# LM317_Voltage_supply_2020-10-09_18-57-09.net
KiCad netlist of a schematic drawn in EasyEDA
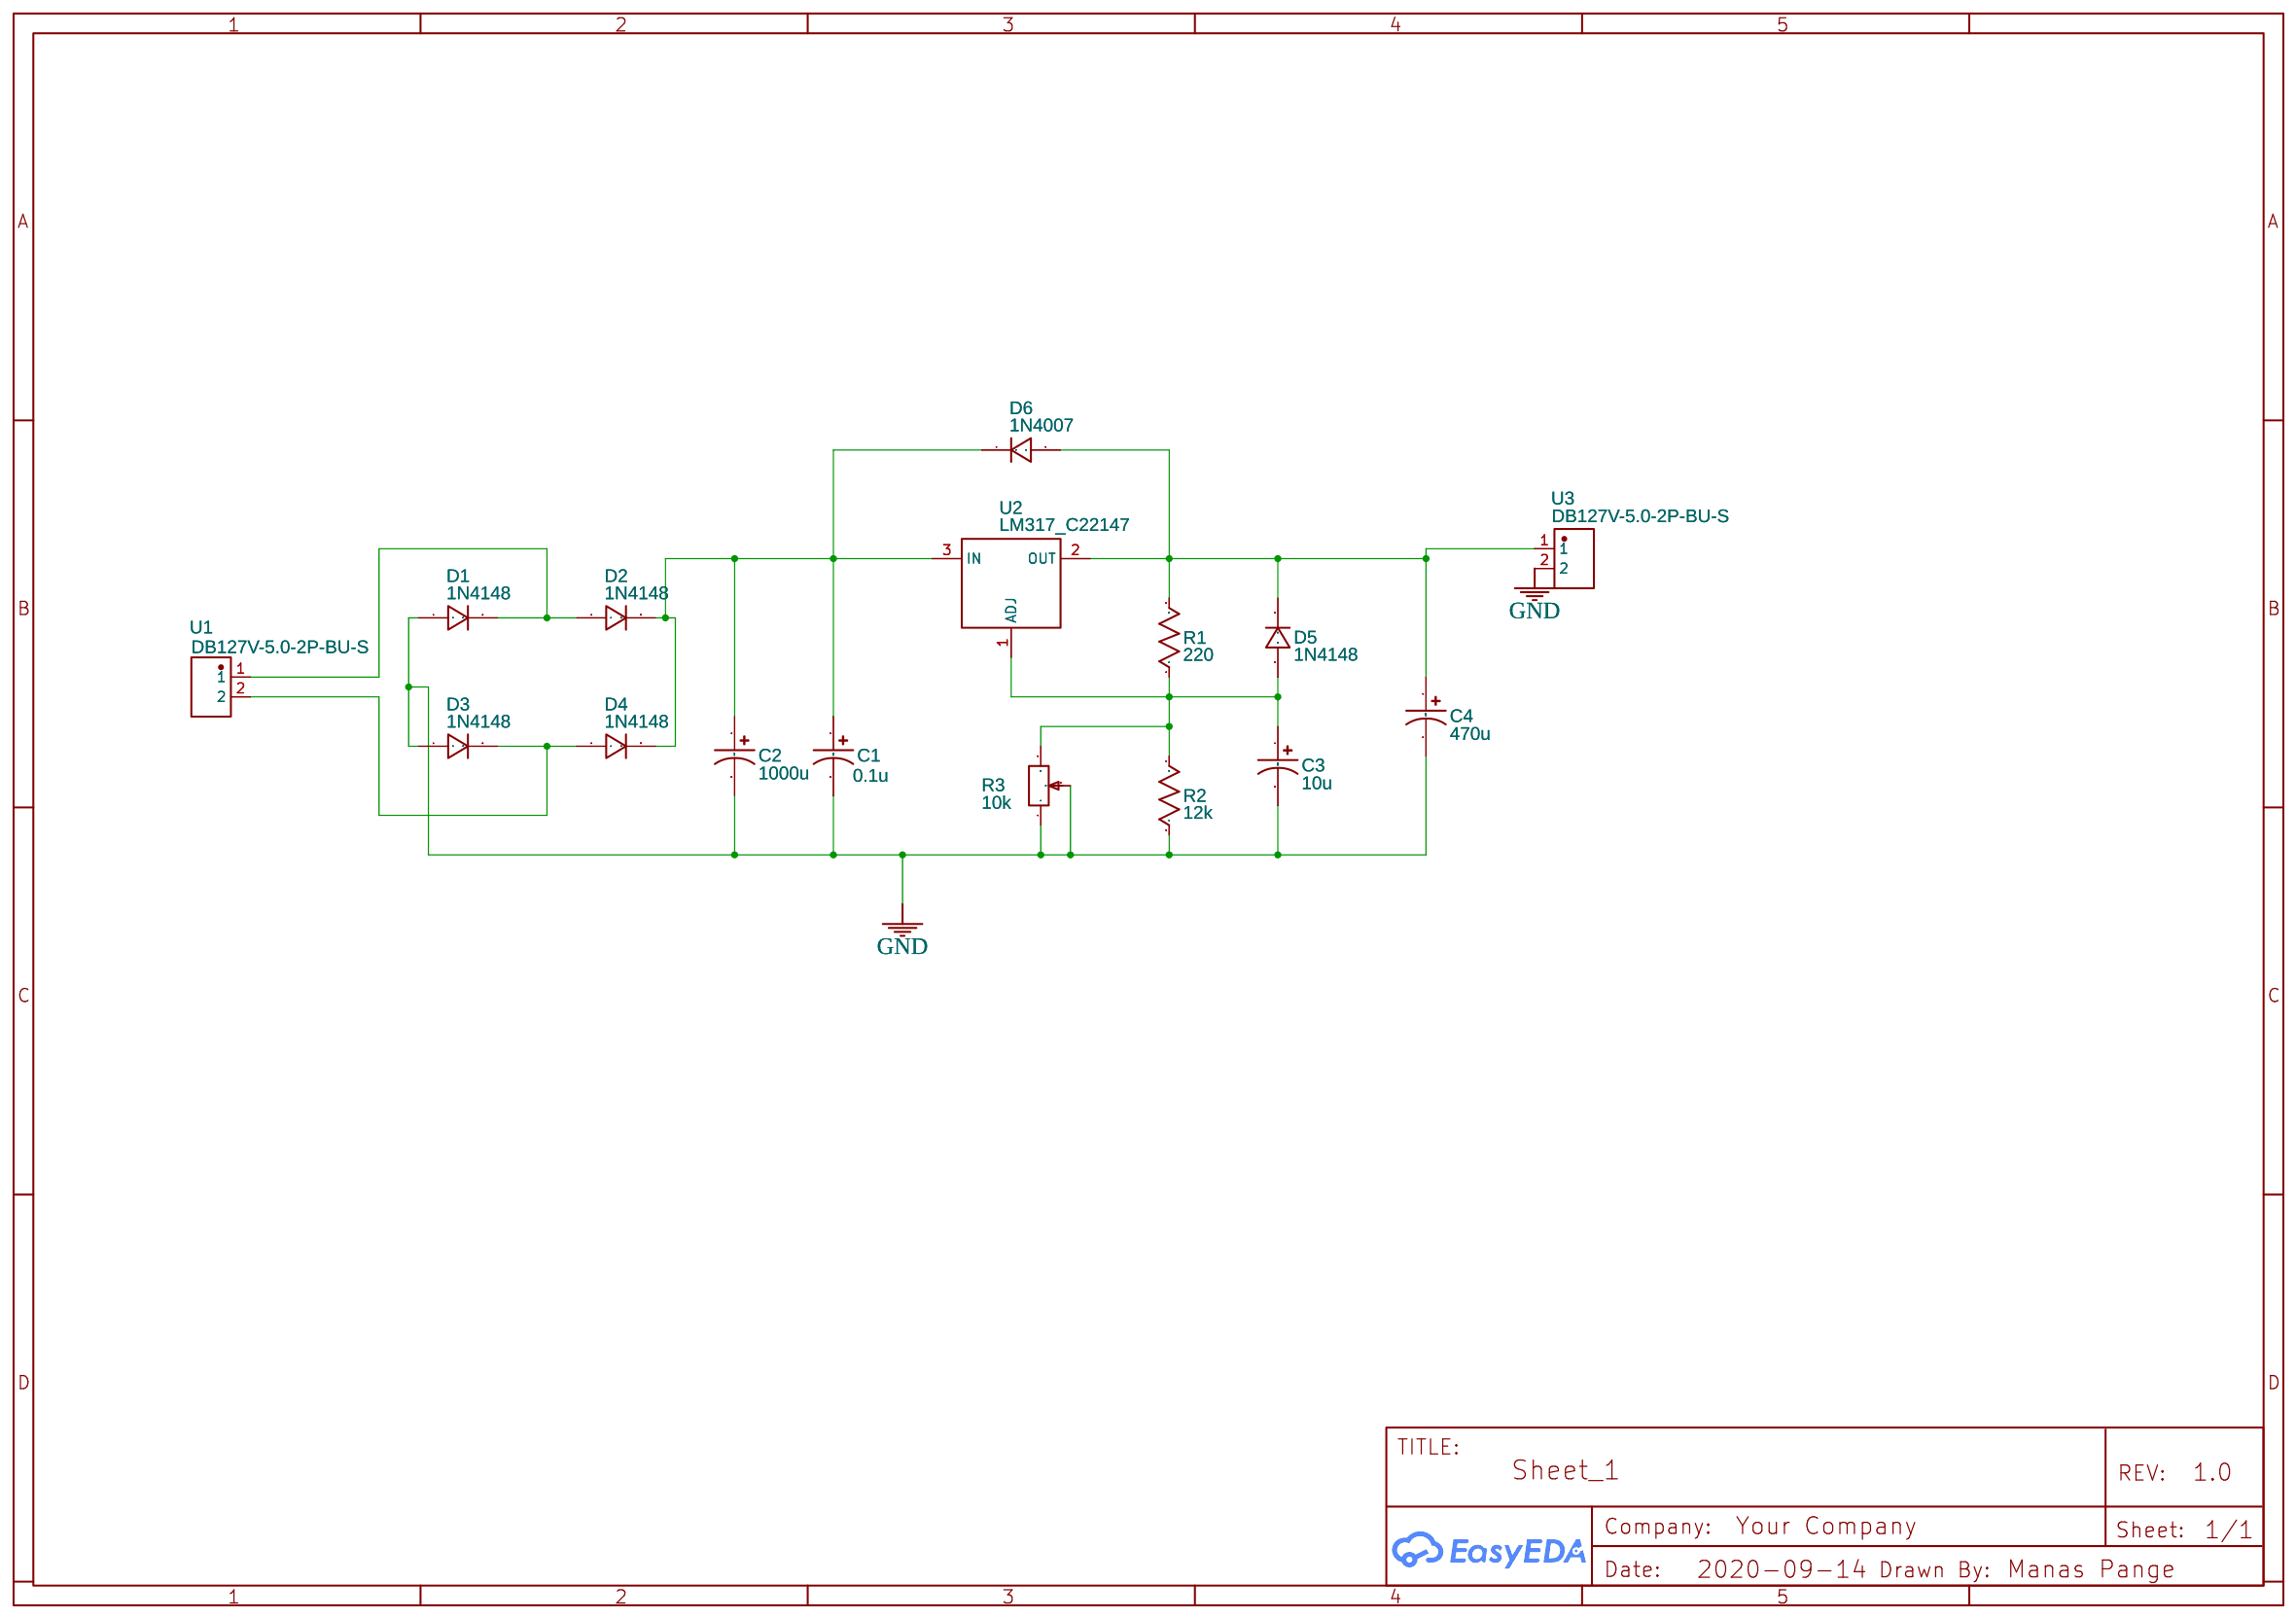
[diagram p0: schematic sheet]

(export (version "E")
  (design (tool "Eeschema 10.0.6"))
  (components
    (comp (ref "C1") (value "0.1u") (libsource (lib "") (part "CE_TH_D6.3×F2.5_US")))
    (comp (ref "C2") (value "1000u") (libsource (lib "") (part "CE_TH_D6.3×F2.5_US")))
    (comp (ref "C3") (value "10u") (libsource (lib "") (part "CE_TH_D6.3×F2.5_US")))
    (comp (ref "C4") (value "470u") (libsource (lib "") (part "CE_TH_D6.3×F2.5_US")))
    (comp (ref "D1")
      (value "1N4148")
      (fields (field (name "BOM_Supplier Part") "C14516"))
      (libsource (lib "") (part "1N4148"))
    )
    (comp (ref "D2")
      (value "1N4148")
      (fields (field (name "BOM_Supplier Part") "C14516"))
      (libsource (lib "") (part "1N4148"))
    )
    (comp (ref "D3")
      (value "1N4148")
      (fields (field (name "BOM_Supplier Part") "C14516"))
      (libsource (lib "") (part "1N4148"))
    )
    (comp (ref "D4")
      (value "1N4148")
      (fields (field (name "BOM_Supplier Part") "C14516"))
      (libsource (lib "") (part "1N4148"))
    )
    (comp (ref "D5")
      (value "1N4148")
      (fields (field (name "BOM_Supplier Part") "C14516"))
      (libsource (lib "") (part "1N4148_1"))
    )
    (comp (ref "D6")
      (value "1N4007")
      (fields (field (name "BOM_Supplier Part") "C106903"))
      (libsource (lib "") (part "1N4007"))
    )
    (comp (ref "R1") (value "220") (libsource (lib "") (part "R_AXIAL-0.3_US")))
    (comp (ref "R2") (value "12k") (libsource (lib "") (part "R_AXIAL-0.3_US")))
    (comp (ref "R3")
      (value "10k")
      (fields
        (field (name "BOM_Manufacturer Part") "RK1631110TT3")
        (field (name "BOM_Supplier Part") "C370977")
      )
      (libsource (lib "") (part "RK1631110TT3"))
    )
    (comp (ref "U1")
      (value "DB127V-5.0-2P-BU-S")
      (fields (field (name "BOM_Supplier Part") "C500019"))
      (libsource (lib "") (part "DB127V-5.0-2P-BU-S_1"))
    )
    (comp (ref "U2")
      (value "LM317_C22147")
      (fields (field (name "BOM_Manufacturer Part") "LM317") (field (name "BOM_Supplier Part") "C22147"))
      (libsource (lib "") (part "LM317_C22147"))
    )
    (comp (ref "U3")
      (value "DB127V-5.0-2P-BU-S")
      (fields (field (name "BOM_Supplier Part") "C500019"))
      (libsource (lib "") (part "DB127V-5.0-2P-BU-S"))
    )
  )
  (nets
    (net (code "1") (name "GND") (class "Default")
      (node (ref "C1") (pin "2") (pinfunction "2_2") (pintype "unspecified"))
      (node (ref "C2") (pin "2") (pinfunction "2_2") (pintype "unspecified"))
      (node (ref "C3") (pin "2") (pinfunction "2_2") (pintype "unspecified"))
      (node (ref "C4") (pin "2") (pinfunction "2_2") (pintype "unspecified"))
      (node (ref "D1") (pin "1") (pinfunction "1_1") (pintype "unspecified"))
      (node (ref "D3") (pin "1") (pinfunction "1_1") (pintype "unspecified"))
      (node (ref "R2") (pin "1") (pinfunction "1_1") (pintype "unspecified"))
      (node (ref "R3") (pin "1") (pinfunction "1_1") (pintype "input"))
      (node (ref "R3") (pin "2") (pinfunction "2_2") (pintype "input"))
      (node (ref "U3") (pin "2") (pinfunction "2_2") (pintype "unspecified"))
    )
    (net (code "2") (name "Net-(D1-Pad2)") (class "Default")
      (node (ref "D1") (pin "2") (pinfunction "2_2") (pintype "unspecified"))
      (node (ref "D2") (pin "1") (pinfunction "1_1") (pintype "unspecified"))
      (node (ref "U1") (pin "1") (pinfunction "1_1") (pintype "unspecified"))
    )
    (net (code "3") (name "Net-(D3-Pad2)") (class "Default")
      (node (ref "D3") (pin "2") (pinfunction "2_2") (pintype "unspecified"))
      (node (ref "D4") (pin "1") (pinfunction "1_1") (pintype "unspecified"))
      (node (ref "U1") (pin "2") (pinfunction "2_2") (pintype "unspecified"))
    )
    (net (code "4") (name "Net-(U2-ADJ)") (class "Default")
      (node (ref "C3") (pin "1") (pinfunction "1_1") (pintype "unspecified"))
      (node (ref "D5") (pin "1") (pinfunction "1_1") (pintype "unspecified"))
      (node (ref "R1") (pin "1") (pinfunction "1_1") (pintype "unspecified"))
      (node (ref "R2") (pin "2") (pinfunction "2_2") (pintype "unspecified"))
      (node (ref "R3") (pin "3") (pinfunction "3_3") (pintype "input"))
      (node (ref "U2") (pin "1") (pinfunction "ADJ_1") (pintype "input"))
    )
    (net (code "5") (name "Net-(U2-IN)") (class "Default")
      (node (ref "C1") (pin "1") (pinfunction "1_1") (pintype "unspecified"))
      (node (ref "C2") (pin "1") (pinfunction "1_1") (pintype "unspecified"))
      (node (ref "D2") (pin "2") (pinfunction "2_2") (pintype "unspecified"))
      (node (ref "D4") (pin "2") (pinfunction "2_2") (pintype "unspecified"))
      (node (ref "D6") (pin "1") (pinfunction "1_1") (pintype "unspecified"))
      (node (ref "U2") (pin "3") (pinfunction "IN_3") (pintype "input"))
    )
    (net (code "6") (name "Net-(U2-OUT)") (class "Default")
      (node (ref "C4") (pin "1") (pinfunction "1_1") (pintype "unspecified"))
      (node (ref "D5") (pin "2") (pinfunction "2_2") (pintype "unspecified"))
      (node (ref "D6") (pin "2") (pinfunction "2_2") (pintype "unspecified"))
      (node (ref "R1") (pin "2") (pinfunction "2_2") (pintype "unspecified"))
      (node (ref "U2") (pin "2") (pinfunction "OUT_2") (pintype "unspecified"))
      (node (ref "U3") (pin "1") (pinfunction "1_1") (pintype "unspecified"))
    )
  )
)
